# ct_micro.net
KiCad netlist of a schematic drawn in Altium Designer
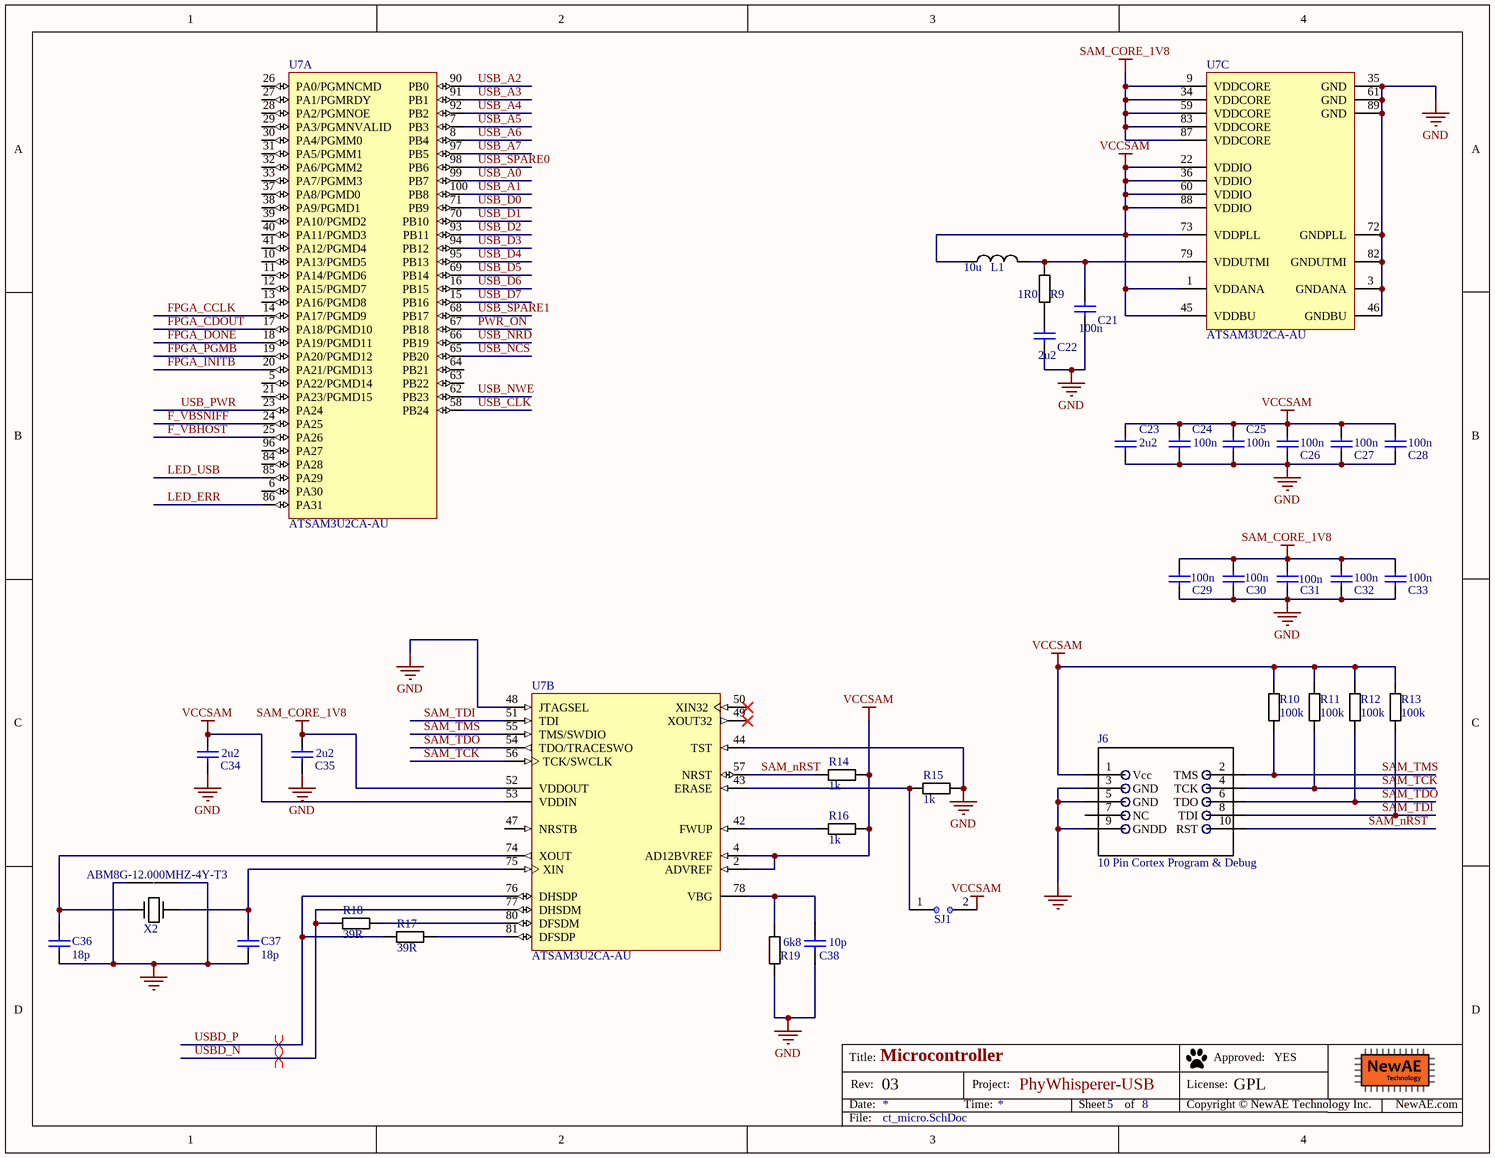
[diagram p0: ct_micro.SchDoc]

(export (version "E")
  (design (tool "Eeschema 10.0.6"))
  (components
    (comp (ref "C21")
      (value "100n")
      (footprint "CAPC0402_M")
      (description "100n, 0402")
      (fields (field (name "PART NUMBER") "CCHIP-100n-0402"))
      (libsource (lib "NewAE_AltiumLib") (part "CAP"))
    )
    (comp (ref "C22")
      (value "2u2")
      (footprint "CAPC0603_M")
      (description "2u2, 0603")
      (fields (field (name "PART NUMBER") "CCHIP-2u2-0603"))
      (libsource (lib "NewAE_AltiumLib") (part "CAP"))
    )
    (comp (ref "C23")
      (value "2u2")
      (footprint "CAPC0603_M")
      (description "2u2, 0603")
      (fields (field (name "PART NUMBER") "CCHIP-2u2-0603"))
      (libsource (lib "NewAE_AltiumLib") (part "CAP"))
    )
    (comp (ref "C24")
      (value "100n")
      (footprint "CAPC0402_M")
      (description "100n, 0402")
      (fields (field (name "PART NUMBER") "CCHIP-100n-0402"))
      (libsource (lib "NewAE_AltiumLib") (part "CAP"))
    )
    (comp (ref "C25")
      (value "100n")
      (footprint "CAPC0402_M")
      (description "100n, 0402")
      (fields (field (name "PART NUMBER") "CCHIP-100n-0402"))
      (libsource (lib "NewAE_AltiumLib") (part "CAP"))
    )
    (comp (ref "C26")
      (value "100n")
      (footprint "CAPC0402_M")
      (description "100n, 0402")
      (fields (field (name "PART NUMBER") "CCHIP-100n-0402"))
      (libsource (lib "NewAE_AltiumLib") (part "CAP"))
    )
    (comp (ref "C27")
      (value "100n")
      (footprint "CAPC0402_M")
      (description "100n, 0402")
      (fields (field (name "PART NUMBER") "CCHIP-100n-0402"))
      (libsource (lib "NewAE_AltiumLib") (part "CAP"))
    )
    (comp (ref "C28")
      (value "100n")
      (footprint "CAPC0402_M")
      (description "100n, 0402")
      (fields (field (name "PART NUMBER") "CCHIP-100n-0402"))
      (libsource (lib "NewAE_AltiumLib") (part "CAP"))
    )
    (comp (ref "C29")
      (value "100n")
      (footprint "CAPC0402_M")
      (description "100n, 0402")
      (fields (field (name "PART NUMBER") "CCHIP-100n-0402"))
      (libsource (lib "NewAE_AltiumLib") (part "CAP"))
    )
    (comp (ref "C30")
      (value "100n")
      (footprint "CAPC0402_M")
      (description "100n, 0402")
      (fields (field (name "PART NUMBER") "CCHIP-100n-0402"))
      (libsource (lib "NewAE_AltiumLib") (part "CAP"))
    )
    (comp (ref "C31")
      (value "100n")
      (footprint "CAPC0402_M")
      (description "100n, 0402")
      (fields (field (name "PART NUMBER") "CCHIP-100n-0402"))
      (libsource (lib "NewAE_AltiumLib") (part "CAP"))
    )
    (comp (ref "C32")
      (value "100n")
      (footprint "CAPC0402_M")
      (description "100n, 0402")
      (fields (field (name "PART NUMBER") "CCHIP-100n-0402"))
      (libsource (lib "NewAE_AltiumLib") (part "CAP"))
    )
    (comp (ref "C33")
      (value "100n")
      (footprint "CAPC0402_M")
      (description "100n, 0402")
      (fields (field (name "PART NUMBER") "CCHIP-100n-0402"))
      (libsource (lib "NewAE_AltiumLib") (part "CAP"))
    )
    (comp (ref "C34")
      (value "2u2")
      (footprint "CAPC0603_M")
      (description "2u2, 0603")
      (fields (field (name "PART NUMBER") "CCHIP-2u2-0603"))
      (libsource (lib "NewAE_AltiumLib") (part "CAP"))
    )
    (comp (ref "C35")
      (value "2u2")
      (footprint "CAPC0603_M")
      (description "2u2, 0603")
      (fields (field (name "PART NUMBER") "CCHIP-2u2-0603"))
      (libsource (lib "NewAE_AltiumLib") (part "CAP"))
    )
    (comp (ref "C36")
      (value "18p")
      (footprint "CAPC0402_M")
      (description "18p, 0402")
      (fields (field (name "PART NUMBER") "CCHIP-18p-0402"))
      (libsource (lib "NewAE_AltiumLib") (part "CAP"))
    )
    (comp (ref "C37")
      (value "18p")
      (footprint "CAPC0402_M")
      (description "18p, 0402")
      (fields (field (name "PART NUMBER") "CCHIP-18p-0402"))
      (libsource (lib "NewAE_AltiumLib") (part "CAP"))
    )
    (comp (ref "C38")
      (value "10p")
      (footprint "CAPC0603_M")
      (description "10p, 0603")
      (fields (field (name "PART NUMBER") "CCHIP-10p-0603"))
      (libsource (lib "NewAE_AltiumLib") (part "CAP"))
    )
    (comp (ref "J6")
      (value "10 Pin Cortex Program & Debug")
      (footprint "0.5mm_SMD_Header_5x2")
      (description "10 Pin Cortex Program & Debug 0.5mm pitch")
      (fields (field (name "PART NUMBER") "Cortex_Debug_Header_10Pin"))
      (libsource (lib "NewAE_AltiumLib") (part "Cortex_Debug_Header_10Pin"))
    )
    (comp (ref "L1")
      (value "10u")
      (footprint "IND_0603")
      (description "FIXED IND 10UH 50MA 900 MOHM SMD")
      (fields (field (name "PART NUMBER") "LCHIP-10U-0603") (field (name "TOLERANCE") "±20%"))
      (libsource (lib "NewAE_AltiumLib") (part "IND"))
    )
    (comp (ref "R9")
      (value "1R0")
      (footprint "RESC1608X55N")
      (description "1R0 res, 0603, 1%, 1/10W")
      (fields (field (name "PART NUMBER") "RCHIP-1R0-0603") (field (name "TOLERANCE") "1%"))
      (libsource (lib "NewAE_AltiumLib") (part "RES-EU"))
    )
    (comp (ref "R10")
      (value "100k")
      (footprint "RESC1608X55N")
      (description "100k res, 0603, 1%, 1/10W")
      (fields (field (name "PART NUMBER") "RCHIP-100K-0603") (field (name "TOLERANCE") "1%"))
      (libsource (lib "NewAE_AltiumLib") (part "RES-EU"))
    )
    (comp (ref "R11")
      (value "100k")
      (footprint "RESC1608X55N")
      (description "100k res, 0603, 1%, 1/10W")
      (fields (field (name "PART NUMBER") "RCHIP-100K-0603") (field (name "TOLERANCE") "1%"))
      (libsource (lib "NewAE_AltiumLib") (part "RES-EU"))
    )
    (comp (ref "R12")
      (value "100k")
      (footprint "RESC1608X55N")
      (description "100k res, 0603, 1%, 1/10W")
      (fields (field (name "PART NUMBER") "RCHIP-100K-0603") (field (name "TOLERANCE") "1%"))
      (libsource (lib "NewAE_AltiumLib") (part "RES-EU"))
    )
    (comp (ref "R13")
      (value "100k")
      (footprint "RESC1608X55N")
      (description "100k res, 0603, 1%, 1/10W")
      (fields (field (name "PART NUMBER") "RCHIP-100K-0603") (field (name "TOLERANCE") "1%"))
      (libsource (lib "NewAE_AltiumLib") (part "RES-EU"))
    )
    (comp (ref "R14")
      (value "1k")
      (footprint "RESC1608X55N")
      (description "1k res, 0603, 1%, 1/10W")
      (fields (field (name "PART NUMBER") "RCHIP-1K-0603") (field (name "TOLERANCE") "1%"))
      (libsource (lib "") (part "RES-EU_1"))
    )
    (comp (ref "R15")
      (value "1k")
      (footprint "RESC1608X55N")
      (description "1k res, 0603, 1%, 1/10W")
      (fields (field (name "PART NUMBER") "RCHIP-1K-0603") (field (name "TOLERANCE") "1%"))
      (libsource (lib "") (part "RES-EU_1"))
    )
    (comp (ref "R16")
      (value "1k")
      (footprint "RESC1608X55N")
      (description "1k res, 0603, 1%, 1/10W")
      (fields (field (name "PART NUMBER") "RCHIP-1K-0603") (field (name "TOLERANCE") "1%"))
      (libsource (lib "") (part "RES-EU_1"))
    )
    (comp (ref "R17")
      (value "39R")
      (footprint "RESC1608X55N")
      (description "39R res, 0603, 1%, 1/10W")
      (fields (field (name "PART NUMBER") "RCHIP-39R-0603") (field (name "TOLERANCE") "1%"))
      (libsource (lib "") (part "RES-EU_1"))
    )
    (comp (ref "R18")
      (value "39R")
      (footprint "RESC1608X55N")
      (description "39R res, 0603, 1%, 1/10W")
      (fields (field (name "PART NUMBER") "RCHIP-39R-0603") (field (name "TOLERANCE") "1%"))
      (libsource (lib "") (part "RES-EU_1"))
    )
    (comp (ref "R19")
      (value "6k8")
      (footprint "RESC1608X55N")
      (description "6k8 res, 0603, 1%, 1/10W")
      (fields (field (name "PART NUMBER") "RCHIP-6K8-0603") (field (name "TOLERANCE") "1%"))
      (libsource (lib "NewAE_AltiumLib") (part "RES-EU"))
    )
    (comp (ref "SJ1")
      (value "NO")
      (footprint "SJ_2S_NO")
      (description "Solder Jumper, NO")
      (fields (field (name "PART NUMBER") "SJ_2S_NO"))
      (libsource (lib "NewAE_AltiumLib") (part "SJ_2S_NO"))
    )
    (comp (ref "U7")
      (value "ATSAM3U2CA-AU")
      (footprint "LQFP100_L")
      (libsource (lib "Altium Content Vault") (part "MC-16B-ATSAM3U-SQ100"))
    )
    (comp (ref "X2")
      (value "ABM8G-12.000MHZ-4Y-T3")
      (footprint "ABM8G")
      (description "CRYSTAL 12.0000MHZ 10PF SMD")
      (libsource (lib "NewAE_AltiumLib") (part "XTAL_4PIN_13"))
    )
  )
  (nets
    (net (code "1") (name "/FPGA_CCLK") (class "Default")
      (node (ref "U7") (pin "14") (pinfunction "PA17/PGMD9_14") (pintype "bidirectional"))
    )
    (net (code "2") (name "/FPGA_CDOUT") (class "Default")
      (node (ref "U7") (pin "17") (pinfunction "PA18/PGMD10_17") (pintype "bidirectional"))
    )
    (net (code "3") (name "/FPGA_DONE") (class "Default")
      (node (ref "U7") (pin "18") (pinfunction "PA19/PGMD11_18") (pintype "bidirectional"))
    )
    (net (code "4") (name "/FPGA_INITB") (class "Default")
      (node (ref "U7") (pin "20") (pinfunction "PA21/PGMD13_20") (pintype "bidirectional"))
    )
    (net (code "5") (name "/FPGA_PGMB") (class "Default")
      (node (ref "U7") (pin "19") (pinfunction "PA20/PGMD12_19") (pintype "bidirectional"))
    )
    (net (code "6") (name "/F_VBHOST") (class "Default")
      (node (ref "U7") (pin "25") (pinfunction "PA26_25") (pintype "bidirectional"))
    )
    (net (code "7") (name "/F_VBSNIFF") (class "Default")
      (node (ref "U7") (pin "24") (pinfunction "PA25_24") (pintype "bidirectional"))
    )
    (net (code "8") (name "/LED_ERR") (class "Default")
      (node (ref "U7") (pin "86") (pinfunction "PA31_86") (pintype "bidirectional"))
    )
    (net (code "9") (name "/LED_USB") (class "Default")
      (node (ref "U7") (pin "85") (pinfunction "PA29_85") (pintype "bidirectional"))
    )
    (net (code "10") (name "/PWR_ON") (class "Default")
      (node (ref "U7") (pin "67") (pinfunction "PB18_67") (pintype "bidirectional"))
    )
    (net (code "11") (name "/SAM_TCK") (class "Default")
      (node (ref "J6") (pin "4") (pinfunction "TCK_4") (pintype "passive"))
      (node (ref "R11") (pin "2") (pinfunction "2_2") (pintype "passive"))
      (node (ref "U7") (pin "56") (pinfunction "TCK/SWCLK_56") (pintype "input"))
    )
    (net (code "12") (name "/SAM_TDI") (class "Default")
      (node (ref "J6") (pin "8") (pinfunction "TDI_8") (pintype "passive"))
      (node (ref "R13") (pin "2") (pinfunction "2_2") (pintype "passive"))
      (node (ref "U7") (pin "51") (pinfunction "TDI_51") (pintype "input"))
    )
    (net (code "13") (name "/SAM_TDO") (class "Default")
      (node (ref "J6") (pin "6") (pinfunction "TDO_6") (pintype "passive"))
      (node (ref "R12") (pin "2") (pinfunction "2_2") (pintype "passive"))
      (node (ref "U7") (pin "54") (pinfunction "TDO/TRACESWO_54") (pintype "output"))
    )
    (net (code "14") (name "/SAM_TMS") (class "Default")
      (node (ref "J6") (pin "2") (pinfunction "TMS_2") (pintype "passive"))
      (node (ref "R10") (pin "2") (pinfunction "2_2") (pintype "passive"))
      (node (ref "U7") (pin "55") (pinfunction "TMS/SWDIO_55") (pintype "input"))
    )
    (net (code "15") (name "/SAM_nRST") (class "Default")
      (node (ref "J6") (pin "10") (pinfunction "RST_10") (pintype "passive"))
      (node (ref "R14") (pin "1") (pinfunction "1_1") (pintype "passive"))
      (node (ref "U7") (pin "57") (pinfunction "NRST_57") (pintype "bidirectional"))
    )
    (net (code "16") (name "/USBD_N") (class "Default")
      (node (ref "R18") (pin "1") (pinfunction "1_1") (pintype "passive"))
      (node (ref "U7") (pin "77") (pinfunction "DHSDM_77") (pintype "bidirectional"))
    )
    (net (code "17") (name "/USBD_P") (class "Default")
      (node (ref "R17") (pin "1") (pinfunction "1_1") (pintype "passive"))
      (node (ref "U7") (pin "76") (pinfunction "DHSDP_76") (pintype "bidirectional"))
    )
    (net (code "18") (name "/USB_A0") (class "Default")
      (node (ref "U7") (pin "99") (pinfunction "PB7_99") (pintype "bidirectional"))
    )
    (net (code "19") (name "/USB_A1") (class "Default")
      (node (ref "U7") (pin "100") (pinfunction "PB8_100") (pintype "bidirectional"))
    )
    (net (code "20") (name "/USB_A2") (class "Default")
      (node (ref "U7") (pin "90") (pinfunction "PB0_90") (pintype "bidirectional"))
    )
    (net (code "21") (name "/USB_A3") (class "Default")
      (node (ref "U7") (pin "91") (pinfunction "PB1_91") (pintype "bidirectional"))
    )
    (net (code "22") (name "/USB_A4") (class "Default")
      (node (ref "U7") (pin "92") (pinfunction "PB2_92") (pintype "bidirectional"))
    )
    (net (code "23") (name "/USB_A5") (class "Default")
      (node (ref "U7") (pin "7") (pinfunction "PB3_7") (pintype "bidirectional"))
    )
    (net (code "24") (name "/USB_A6") (class "Default")
      (node (ref "U7") (pin "8") (pinfunction "PB4_8") (pintype "bidirectional"))
    )
    (net (code "25") (name "/USB_A7") (class "Default")
      (node (ref "U7") (pin "97") (pinfunction "PB5_97") (pintype "bidirectional"))
    )
    (net (code "26") (name "/USB_CLK") (class "Default")
      (node (ref "U7") (pin "58") (pinfunction "PB24_58") (pintype "bidirectional"))
    )
    (net (code "27") (name "/USB_D0") (class "Default")
      (node (ref "U7") (pin "71") (pinfunction "PB9_71") (pintype "bidirectional"))
    )
    (net (code "28") (name "/USB_D1") (class "Default")
      (node (ref "U7") (pin "70") (pinfunction "PB10_70") (pintype "bidirectional"))
    )
    (net (code "29") (name "/USB_D2") (class "Default")
      (node (ref "U7") (pin "93") (pinfunction "PB11_93") (pintype "bidirectional"))
    )
    (net (code "30") (name "/USB_D3") (class "Default")
      (node (ref "U7") (pin "94") (pinfunction "PB12_94") (pintype "bidirectional"))
    )
    (net (code "31") (name "/USB_D4") (class "Default")
      (node (ref "U7") (pin "95") (pinfunction "PB13_95") (pintype "bidirectional"))
    )
    (net (code "32") (name "/USB_D5") (class "Default")
      (node (ref "U7") (pin "69") (pinfunction "PB14_69") (pintype "bidirectional"))
    )
    (net (code "33") (name "/USB_D6") (class "Default")
      (node (ref "U7") (pin "16") (pinfunction "PB15_16") (pintype "bidirectional"))
    )
    (net (code "34") (name "/USB_D7") (class "Default")
      (node (ref "U7") (pin "15") (pinfunction "PB16_15") (pintype "bidirectional"))
    )
    (net (code "35") (name "/USB_NCS") (class "Default")
      (node (ref "U7") (pin "65") (pinfunction "PB20_65") (pintype "bidirectional"))
    )
    (net (code "36") (name "/USB_NRD") (class "Default")
      (node (ref "U7") (pin "66") (pinfunction "PB19_66") (pintype "bidirectional"))
    )
    (net (code "37") (name "/USB_NWE") (class "Default")
      (node (ref "U7") (pin "62") (pinfunction "PB23_62") (pintype "bidirectional"))
    )
    (net (code "38") (name "/USB_PWR") (class "Default")
      (node (ref "U7") (pin "23") (pinfunction "PA24_23") (pintype "bidirectional"))
    )
    (net (code "39") (name "/USB_SPARE0") (class "Default")
      (node (ref "U7") (pin "98") (pinfunction "PB6_98") (pintype "bidirectional"))
    )
    (net (code "40") (name "/USB_SPARE1") (class "Default")
      (node (ref "U7") (pin "68") (pinfunction "PB17_68") (pintype "bidirectional"))
    )
    (net (code "41") (name "GND") (class "Default")
      (node (ref "C21") (pin "2") (pinfunction "2_2") (pintype "passive"))
      (node (ref "C22") (pin "2") (pinfunction "2_2") (pintype "passive"))
      (node (ref "C23") (pin "2") (pinfunction "2_2") (pintype "passive"))
      (node (ref "C24") (pin "2") (pinfunction "2_2") (pintype "passive"))
      (node (ref "C25") (pin "2") (pinfunction "2_2") (pintype "passive"))
      (node (ref "C26") (pin "2") (pinfunction "2_2") (pintype "passive"))
      (node (ref "C27") (pin "2") (pinfunction "2_2") (pintype "passive"))
      (node (ref "C28") (pin "2") (pinfunction "2_2") (pintype "passive"))
      (node (ref "C29") (pin "2") (pinfunction "2_2") (pintype "passive"))
      (node (ref "C30") (pin "2") (pinfunction "2_2") (pintype "passive"))
      (node (ref "C31") (pin "2") (pinfunction "2_2") (pintype "passive"))
      (node (ref "C32") (pin "2") (pinfunction "2_2") (pintype "passive"))
      (node (ref "C33") (pin "2") (pinfunction "2_2") (pintype "passive"))
      (node (ref "C34") (pin "2") (pinfunction "2_2") (pintype "passive"))
      (node (ref "C35") (pin "2") (pinfunction "2_2") (pintype "passive"))
      (node (ref "C36") (pin "2") (pinfunction "2_2") (pintype "passive"))
      (node (ref "C37") (pin "2") (pinfunction "2_2") (pintype "passive"))
      (node (ref "C38") (pin "2") (pinfunction "2_2") (pintype "passive"))
      (node (ref "J6") (pin "3") (pinfunction "GND_3") (pintype "passive"))
      (node (ref "J6") (pin "5") (pinfunction "GND_5") (pintype "passive"))
      (node (ref "J6") (pin "9") (pinfunction "GNDD_9") (pintype "passive"))
      (node (ref "R15") (pin "2") (pinfunction "2_2") (pintype "passive"))
      (node (ref "R19") (pin "2") (pinfunction "2_2") (pintype "passive"))
      (node (ref "U7") (pin "3") (pinfunction "GNDANA_3") (pintype "power_in"))
      (node (ref "U7") (pin "35") (pinfunction "GND_35") (pintype "power_in"))
      (node (ref "U7") (pin "44") (pinfunction "TST_44") (pintype "input"))
      (node (ref "U7") (pin "46") (pinfunction "GNDBU_46") (pintype "power_in"))
      (node (ref "U7") (pin "48") (pinfunction "JTAGSEL_48") (pintype "input"))
      (node (ref "U7") (pin "61") (pinfunction "GND_61") (pintype "power_in"))
      (node (ref "U7") (pin "72") (pinfunction "GNDPLL_72") (pintype "power_in"))
      (node (ref "U7") (pin "82") (pinfunction "GNDUTMI_82") (pintype "power_in"))
      (node (ref "U7") (pin "89") (pinfunction "GND_89") (pintype "power_in"))
      (node (ref "X2") (pin "2") (pinfunction "GND_2") (pintype "power_in"))
      (node (ref "X2") (pin "4") (pinfunction "GND_4") (pintype "power_in"))
    )
    (net (code "42") (name "Net-(C22-Pad1)") (class "Default")
      (node (ref "C22") (pin "1") (pinfunction "1_1") (pintype "passive"))
      (node (ref "R9") (pin "2") (pinfunction "2_2") (pintype "passive"))
    )
    (net (code "43") (name "Net-(U7B-DFSDM)") (class "Default")
      (node (ref "R18") (pin "2") (pinfunction "2_2") (pintype "passive"))
      (node (ref "U7") (pin "80") (pinfunction "DFSDM_80") (pintype "bidirectional"))
    )
    (net (code "44") (name "Net-(U7B-DFSDP)") (class "Default")
      (node (ref "R17") (pin "2") (pinfunction "2_2") (pintype "passive"))
      (node (ref "U7") (pin "81") (pinfunction "DFSDP_81") (pintype "bidirectional"))
    )
    (net (code "45") (name "Net-(U7B-ERASE)") (class "Default")
      (node (ref "R15") (pin "1") (pinfunction "1_1") (pintype "passive"))
      (node (ref "SJ1") (pin "1") (pinfunction "1_1") (pintype "passive"))
      (node (ref "U7") (pin "43") (pinfunction "ERASE_43") (pintype "input"))
    )
    (net (code "46") (name "Net-(U7B-FWUP)") (class "Default")
      (node (ref "R16") (pin "1") (pinfunction "1_1") (pintype "passive"))
      (node (ref "U7") (pin "42") (pinfunction "FWUP_42") (pintype "input"))
    )
    (net (code "47") (name "Net-(U7B-VBG)") (class "Default")
      (node (ref "C38") (pin "1") (pinfunction "1_1") (pintype "passive"))
      (node (ref "R19") (pin "1") (pinfunction "1_1") (pintype "passive"))
      (node (ref "U7") (pin "78") (pinfunction "VBG_78") (pintype "passive"))
    )
    (net (code "48") (name "Net-(U7B-XIN)") (class "Default")
      (node (ref "C37") (pin "1") (pinfunction "1_1") (pintype "passive"))
      (node (ref "U7") (pin "75") (pinfunction "XIN_75") (pintype "input"))
      (node (ref "X2") (pin "3") (pinfunction "OUT_3") (pintype "passive"))
    )
    (net (code "49") (name "Net-(U7B-XOUT)") (class "Default")
      (node (ref "C36") (pin "1") (pinfunction "1_1") (pintype "passive"))
      (node (ref "U7") (pin "74") (pinfunction "XOUT_74") (pintype "output"))
      (node (ref "X2") (pin "1") (pinfunction "IN_1") (pintype "passive"))
    )
    (net (code "50") (name "Net-(U7C-VDDUTMI)") (class "Default")
      (node (ref "C21") (pin "1") (pinfunction "1_1") (pintype "passive"))
      (node (ref "L1") (pin "2") (pinfunction "2_2") (pintype "passive"))
      (node (ref "R9") (pin "1") (pinfunction "1_1") (pintype "passive"))
      (node (ref "U7") (pin "79") (pinfunction "VDDUTMI_79") (pintype "power_in"))
    )
    (net (code "51") (name "SAM_CORE_1V8") (class "Default")
      (node (ref "C29") (pin "1") (pinfunction "1_1") (pintype "passive"))
      (node (ref "C30") (pin "1") (pinfunction "1_1") (pintype "passive"))
      (node (ref "C31") (pin "1") (pinfunction "1_1") (pintype "passive"))
      (node (ref "C32") (pin "1") (pinfunction "1_1") (pintype "passive"))
      (node (ref "C33") (pin "1") (pinfunction "1_1") (pintype "passive"))
      (node (ref "C35") (pin "1") (pinfunction "1_1") (pintype "passive"))
      (node (ref "U7") (pin "34") (pinfunction "VDDCORE_34") (pintype "power_in"))
      (node (ref "U7") (pin "52") (pinfunction "VDDOUT_52") (pintype "power_in"))
      (node (ref "U7") (pin "59") (pinfunction "VDDCORE_59") (pintype "power_in"))
      (node (ref "U7") (pin "83") (pinfunction "VDDCORE_83") (pintype "power_in"))
      (node (ref "U7") (pin "87") (pinfunction "VDDCORE_87") (pintype "power_in"))
      (node (ref "U7") (pin "9") (pinfunction "VDDCORE_9") (pintype "power_in"))
    )
    (net (code "52") (name "VCCSAM") (class "Default")
      (node (ref "C23") (pin "1") (pinfunction "1_1") (pintype "passive"))
      (node (ref "C24") (pin "1") (pinfunction "1_1") (pintype "passive"))
      (node (ref "C25") (pin "1") (pinfunction "1_1") (pintype "passive"))
      (node (ref "C26") (pin "1") (pinfunction "1_1") (pintype "passive"))
      (node (ref "C27") (pin "1") (pinfunction "1_1") (pintype "passive"))
      (node (ref "C28") (pin "1") (pinfunction "1_1") (pintype "passive"))
      (node (ref "C34") (pin "1") (pinfunction "1_1") (pintype "passive"))
      (node (ref "J6") (pin "1") (pinfunction "Vcc_1") (pintype "passive"))
      (node (ref "L1") (pin "1") (pinfunction "1_1") (pintype "passive"))
      (node (ref "R10") (pin "1") (pinfunction "1_1") (pintype "passive"))
      (node (ref "R11") (pin "1") (pinfunction "1_1") (pintype "passive"))
      (node (ref "R12") (pin "1") (pinfunction "1_1") (pintype "passive"))
      (node (ref "R13") (pin "1") (pinfunction "1_1") (pintype "passive"))
      (node (ref "R14") (pin "2") (pinfunction "2_2") (pintype "passive"))
      (node (ref "R16") (pin "2") (pinfunction "2_2") (pintype "passive"))
      (node (ref "SJ1") (pin "2") (pinfunction "2_2") (pintype "passive"))
      (node (ref "U7") (pin "1") (pinfunction "VDDANA_1") (pintype "power_in"))
      (node (ref "U7") (pin "2") (pinfunction "ADVREF_2") (pintype "input"))
      (node (ref "U7") (pin "22") (pinfunction "VDDIO_22") (pintype "power_in"))
      (node (ref "U7") (pin "36") (pinfunction "VDDIO_36") (pintype "power_in"))
      (node (ref "U7") (pin "4") (pinfunction "AD12BVREF_4") (pintype "input"))
      (node (ref "U7") (pin "45") (pinfunction "VDDBU_45") (pintype "power_in"))
      (node (ref "U7") (pin "53") (pinfunction "VDDIN_53") (pintype "power_in"))
      (node (ref "U7") (pin "60") (pinfunction "VDDIO_60") (pintype "power_in"))
      (node (ref "U7") (pin "73") (pinfunction "VDDPLL_73") (pintype "power_in"))
      (node (ref "U7") (pin "88") (pinfunction "VDDIO_88") (pintype "power_in"))
    )
    (net (code "53") (name "unconnected-(J6-NC-Pad7)") (class "Default")
      (node (ref "J6") (pin "7") (pinfunction "NC_7") (pintype "passive"))
    )
    (net (code "54") (name "unconnected-(U7A-PA0{slash}PGMNCMD-Pad26)") (class "Default")
      (node (ref "U7") (pin "26") (pinfunction "PA0/PGMNCMD_26") (pintype "bidirectional"))
    )
    (net (code "55") (name "unconnected-(U7A-PA1{slash}PGMRDY-Pad27)") (class "Default")
      (node (ref "U7") (pin "27") (pinfunction "PA1/PGMRDY_27") (pintype "bidirectional"))
    )
    (net (code "56") (name "unconnected-(U7A-PA2{slash}PGMNOE-Pad28)") (class "Default")
      (node (ref "U7") (pin "28") (pinfunction "PA2/PGMNOE_28") (pintype "bidirectional"))
    )
    (net (code "57") (name "unconnected-(U7A-PA3{slash}PGMNVALID-Pad29)") (class "Default")
      (node (ref "U7") (pin "29") (pinfunction "PA3/PGMNVALID_29") (pintype "bidirectional"))
    )
    (net (code "58") (name "unconnected-(U7A-PA4{slash}PGMM0-Pad30)") (class "Default")
      (node (ref "U7") (pin "30") (pinfunction "PA4/PGMM0_30") (pintype "bidirectional"))
    )
    (net (code "59") (name "unconnected-(U7A-PA5{slash}PGMM1-Pad31)") (class "Default")
      (node (ref "U7") (pin "31") (pinfunction "PA5/PGMM1_31") (pintype "bidirectional"))
    )
    (net (code "60") (name "unconnected-(U7A-PA6{slash}PGMM2-Pad32)") (class "Default")
      (node (ref "U7") (pin "32") (pinfunction "PA6/PGMM2_32") (pintype "bidirectional"))
    )
    (net (code "61") (name "unconnected-(U7A-PA7{slash}PGMM3-Pad33)") (class "Default")
      (node (ref "U7") (pin "33") (pinfunction "PA7/PGMM3_33") (pintype "bidirectional"))
    )
    (net (code "62") (name "unconnected-(U7A-PA8{slash}PGMD0-Pad37)") (class "Default")
      (node (ref "U7") (pin "37") (pinfunction "PA8/PGMD0_37") (pintype "bidirectional"))
    )
    (net (code "63") (name "unconnected-(U7A-PA9{slash}PGMD1-Pad38)") (class "Default")
      (node (ref "U7") (pin "38") (pinfunction "PA9/PGMD1_38") (pintype "bidirectional"))
    )
    (net (code "64") (name "unconnected-(U7A-PA10{slash}PGMD2-Pad39)") (class "Default")
      (node (ref "U7") (pin "39") (pinfunction "PA10/PGMD2_39") (pintype "bidirectional"))
    )
    (net (code "65") (name "unconnected-(U7A-PA11{slash}PGMD3-Pad40)") (class "Default")
      (node (ref "U7") (pin "40") (pinfunction "PA11/PGMD3_40") (pintype "bidirectional"))
    )
    (net (code "66") (name "unconnected-(U7A-PA12{slash}PGMD4-Pad41)") (class "Default")
      (node (ref "U7") (pin "41") (pinfunction "PA12/PGMD4_41") (pintype "bidirectional"))
    )
    (net (code "67") (name "unconnected-(U7A-PA13{slash}PGMD5-Pad10)") (class "Default")
      (node (ref "U7") (pin "10") (pinfunction "PA13/PGMD5_10") (pintype "bidirectional"))
    )
    (net (code "68") (name "unconnected-(U7A-PA14{slash}PGMD6-Pad11)") (class "Default")
      (node (ref "U7") (pin "11") (pinfunction "PA14/PGMD6_11") (pintype "bidirectional"))
    )
    (net (code "69") (name "unconnected-(U7A-PA15{slash}PGMD7-Pad12)") (class "Default")
      (node (ref "U7") (pin "12") (pinfunction "PA15/PGMD7_12") (pintype "bidirectional"))
    )
    (net (code "70") (name "unconnected-(U7A-PA16{slash}PGMD8-Pad13)") (class "Default")
      (node (ref "U7") (pin "13") (pinfunction "PA16/PGMD8_13") (pintype "bidirectional"))
    )
    (net (code "71") (name "unconnected-(U7A-PA22{slash}PGMD14-Pad5)") (class "Default")
      (node (ref "U7") (pin "5") (pinfunction "PA22/PGMD14_5") (pintype "bidirectional"))
    )
    (net (code "72") (name "unconnected-(U7A-PA23{slash}PGMD15-Pad21)") (class "Default")
      (node (ref "U7") (pin "21") (pinfunction "PA23/PGMD15_21") (pintype "bidirectional"))
    )
    (net (code "73") (name "unconnected-(U7A-PA27-Pad96)") (class "Default")
      (node (ref "U7") (pin "96") (pinfunction "PA27_96") (pintype "bidirectional"))
    )
    (net (code "74") (name "unconnected-(U7A-PA28-Pad84)") (class "Default")
      (node (ref "U7") (pin "84") (pinfunction "PA28_84") (pintype "bidirectional"))
    )
    (net (code "75") (name "unconnected-(U7A-PA30-Pad6)") (class "Default")
      (node (ref "U7") (pin "6") (pinfunction "PA30_6") (pintype "bidirectional"))
    )
    (net (code "76") (name "unconnected-(U7A-PB21-Pad64)") (class "Default")
      (node (ref "U7") (pin "64") (pinfunction "PB21_64") (pintype "bidirectional"))
    )
    (net (code "77") (name "unconnected-(U7A-PB22-Pad63)") (class "Default")
      (node (ref "U7") (pin "63") (pinfunction "PB22_63") (pintype "bidirectional"))
    )
    (net (code "78") (name "unconnected-(U7B-NRSTB-Pad47)") (class "Default")
      (node (ref "U7") (pin "47") (pinfunction "NRSTB_47") (pintype "input"))
    )
    (net (code "79") (name "unconnected-(U7B-XIN32-Pad50)") (class "Default")
      (node (ref "U7") (pin "50") (pinfunction "XIN32_50") (pintype "input+no_connect"))
    )
    (net (code "80") (name "unconnected-(U7B-XOUT32-Pad49)") (class "Default")
      (node (ref "U7") (pin "49") (pinfunction "XOUT32_49") (pintype "output+no_connect"))
    )
  )
)
